# maus-blenano2-mk-1_0_3.net
KiCad netlist of a schematic drawn in EAGLE
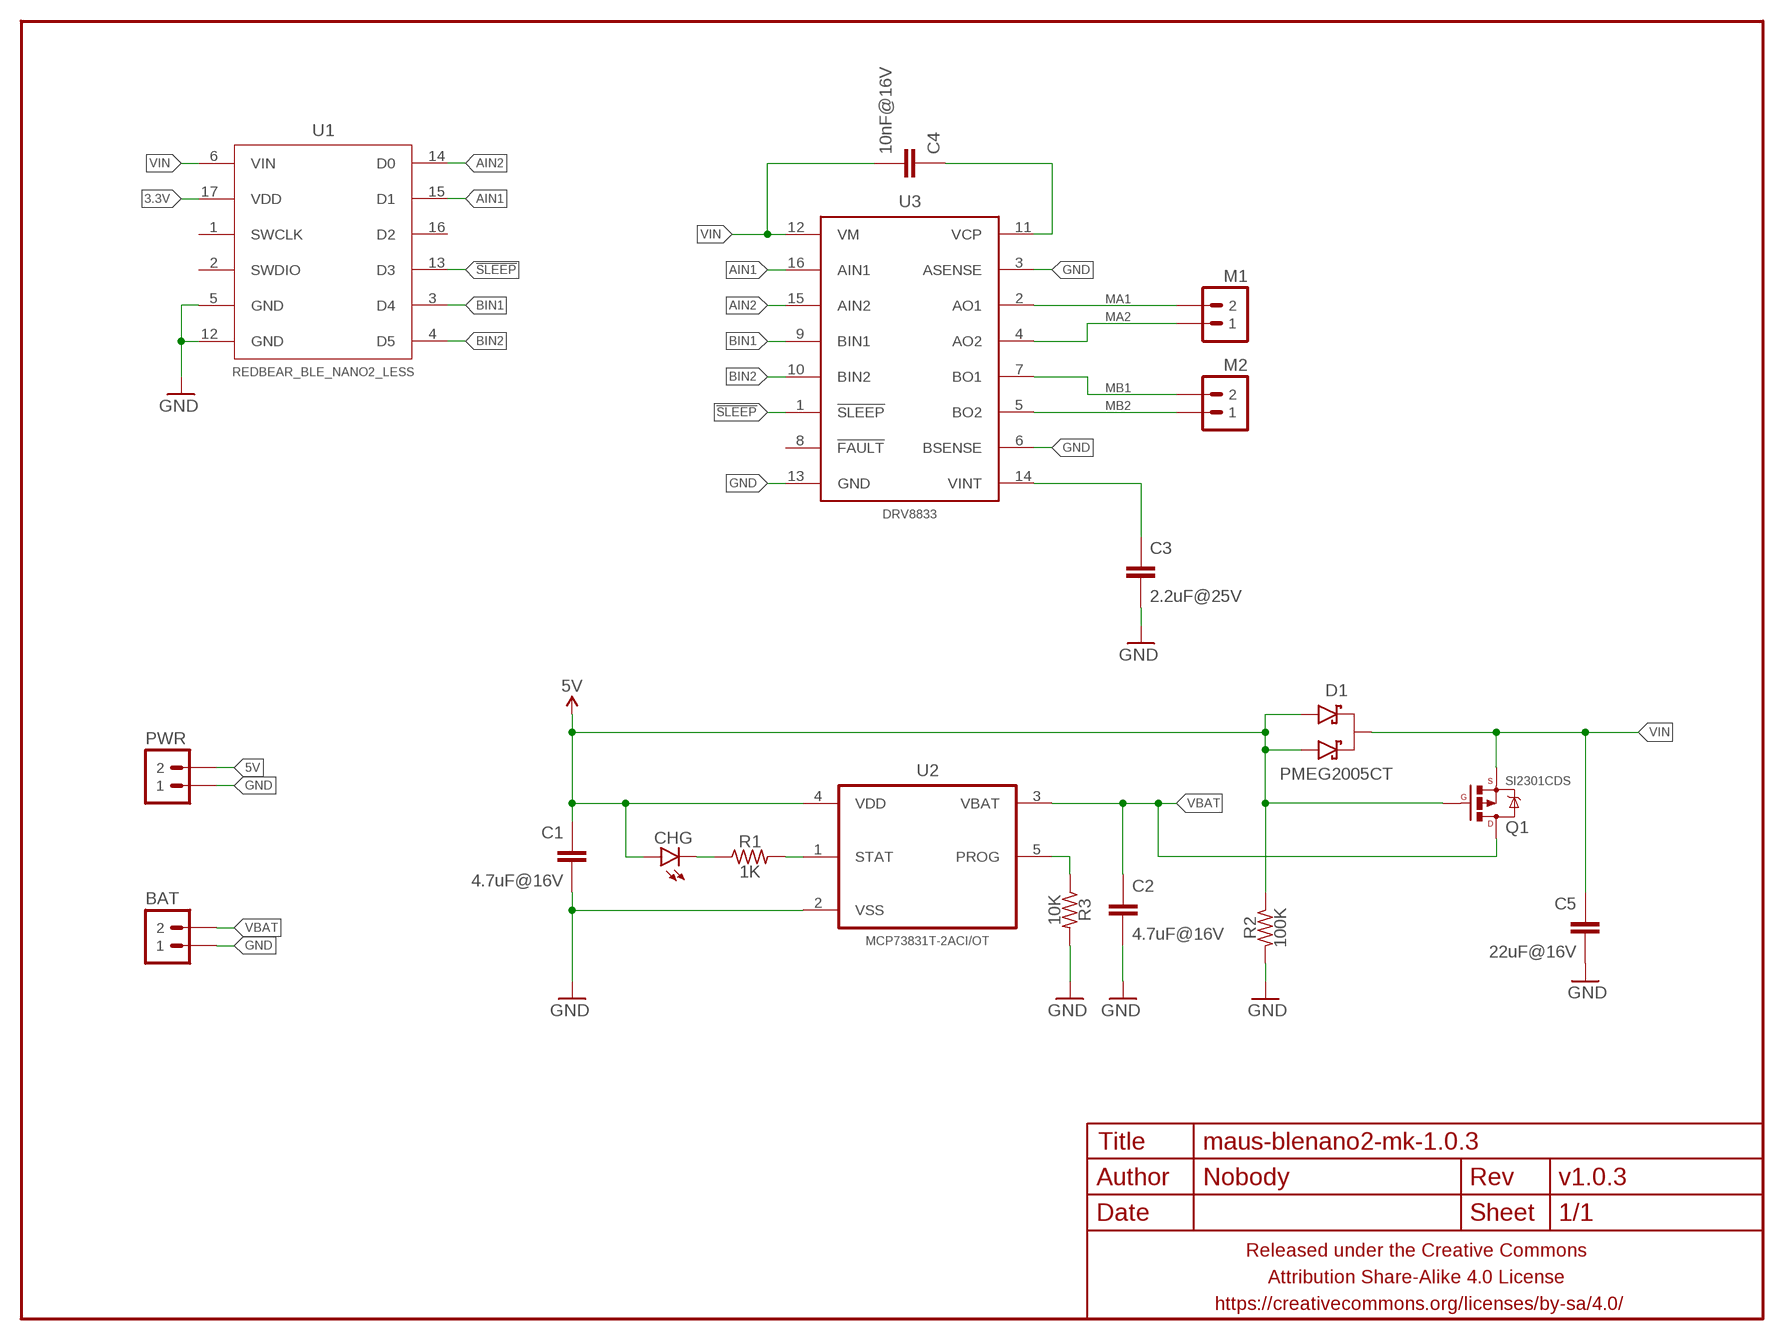
[diagram p0: schematic, sheet 1]

(export (version "E")
  (design (tool "Eeschema 10.0.6"))
  (components
    (comp (ref "BAT")
      (value "M02PTH-2MM")
      (footprint "eagle-import:1X02-2MM-PTH")
      (libsource (lib "eagle-import") (part "M02PTH-2MM"))
    )
    (comp (ref "C1")
      (value "4.7uF@16V")
      (footprint "eagle-import:C0603-TIGHTER")
      (libsource (lib "eagle-import") (part "CAPACITOR-CERAMICC0603-TIGHTER"))
    )
    (comp (ref "C2")
      (value "4.7uF@16V")
      (footprint "eagle-import:C0603-TIGHTER")
      (libsource (lib "eagle-import") (part "CAPACITOR-CERAMICC0603-TIGHTER"))
    )
    (comp (ref "C3")
      (value "2.2uF@25V")
      (footprint "eagle-import:C0603")
      (libsource (lib "eagle-import") (part "CAPACITOR-CERAMICC0603"))
    )
    (comp (ref "C4")
      (value "10nF@16V")
      (footprint "eagle-import:C0402")
      (libsource (lib "eagle-import") (part "CAPACITOR-CERAMICC0402"))
    )
    (comp (ref "C5")
      (value "22uF@16V")
      (footprint "eagle-import:C1206")
      (libsource (lib "eagle-import") (part "CAPACITOR-CERAMICC1206"))
    )
    (comp (ref "CHG")
      (value "LED0603-TIGHT")
      (footprint "eagle-import:LED-0603-TIGHT")
      (libsource (lib "eagle-import") (part "LED0603-TIGHT"))
    )
    (comp (ref "D1")
      (value "PMEG2005CT")
      (footprint "eagle-import:SOT23")
      (libsource (lib "eagle-import") (part "DIODE-SCHOTTKY-DUALPMEG2005CT"))
    )
    (comp (ref "FRAME1")
      (value "FRAME-LETTERNO_PACKAGE")
      (footprint "eagle-import:DUMMY")
      (fields (field (name "VERSION") "v1.0.3") (field (name "DESIGNER") "Nobody"))
      (libsource (lib "eagle-import") (part "FRAME-LETTERNO_PACKAGE"))
    )
    (comp (ref "M1")
      (value "M02PTH-2MM")
      (footprint "eagle-import:1X02-2MM-PTH")
      (libsource (lib "eagle-import") (part "M02PTH-2MM"))
    )
    (comp (ref "M2")
      (value "M02PTH-2MM")
      (footprint "eagle-import:1X02-2MM-PTH")
      (libsource (lib "eagle-import") (part "M02PTH-2MM"))
    )
    (comp (ref "PWR")
      (value "M02PTH-2MM")
      (footprint "eagle-import:1X02-2MM-PTH")
      (libsource (lib "eagle-import") (part "M02PTH-2MM"))
    )
    (comp (ref "Q1")
      (value "SI2301CDS")
      (footprint "eagle-import:SOT23")
      (libsource (lib "eagle-import") (part "MOSFET-PCHANNELSOT-23"))
    )
    (comp (ref "R1")
      (value "1K")
      (footprint "eagle-import:R0603-TIGHTER")
      (libsource (lib "eagle-import") (part "RESISTORR0603-TIGHTER"))
    )
    (comp (ref "R2")
      (value "100K")
      (footprint "eagle-import:R0603-TIGHTER")
      (libsource (lib "eagle-import") (part "RESISTORR0603-TIGHTER"))
    )
    (comp (ref "R3")
      (value "10K")
      (footprint "eagle-import:R0603-TIGHTER")
      (libsource (lib "eagle-import") (part "RESISTORR0603-TIGHTER"))
    )
    (comp (ref "U1")
      (value "REDBEAR_BLE_NANO2_LESS")
      (footprint "eagle-import:REDBEAR_BLE_NANO2_LESS")
      (libsource (lib "eagle-import") (part "REDBEAR_BLE_NANO2_LESS"))
    )
    (comp (ref "U2")
      (value "MCP73831T-2ACI/OT")
      (footprint "eagle-import:SOT95P280X145-5N")
      (libsource (lib "eagle-import") (part "MCP73831T-2ACI/OT"))
    )
    (comp (ref "U3")
      (value "DRV8833")
      (footprint "eagle-import:TSSOP16")
      (libsource (lib "eagle-import") (part "DRV8833PW"))
    )
  )
  (nets
    (net (code "1") (name "/MA1") (class "Default")
      (node (ref "M1") (pin "P$2") (pinfunction "2_P$2") (pintype "passive"))
      (node (ref "U3") (pin "2") (pinfunction "AO1_2") (pintype "bidirectional"))
    )
    (net (code "2") (name "/MA2") (class "Default")
      (node (ref "M1") (pin "P$1") (pinfunction "1_P$1") (pintype "passive"))
      (node (ref "U3") (pin "4") (pinfunction "AO2_4") (pintype "bidirectional"))
    )
    (net (code "3") (name "/MB1") (class "Default")
      (node (ref "M2") (pin "P$2") (pinfunction "2_P$2") (pintype "passive"))
      (node (ref "U3") (pin "7") (pinfunction "BO1_7") (pintype "bidirectional"))
    )
    (net (code "4") (name "/MB2") (class "Default")
      (node (ref "M2") (pin "P$1") (pinfunction "1_P$1") (pintype "passive"))
      (node (ref "U3") (pin "5") (pinfunction "BO2_5") (pintype "bidirectional"))
    )
    (net (code "5") (name "/~{SLEEP}") (class "Default")
      (node (ref "U1") (pin "13") (pinfunction "D3_13") (pintype "bidirectional"))
      (node (ref "U3") (pin "1") (pinfunction "~{SLEEP}_1") (pintype "input"))
    )
    (net (code "6") (name "3.3V") (class "Default")
      (node (ref "U1") (pin "17") (pinfunction "VDD_17") (pintype "bidirectional"))
    )
    (net (code "7") (name "5V") (class "Default")
      (node (ref "C1") (pin "1") (pinfunction "1_1") (pintype "passive"))
      (node (ref "CHG") (pin "A") (pinfunction "A_A") (pintype "passive"))
      (node (ref "D1") (pin "1") (pinfunction "A1_1") (pintype "passive"))
      (node (ref "D1") (pin "2") (pinfunction "A2_2") (pintype "passive"))
      (node (ref "PWR") (pin "P$2") (pinfunction "2_P$2") (pintype "passive"))
      (node (ref "Q1") (pin "1") (pinfunction "G_1") (pintype "passive"))
      (node (ref "R2") (pin "1") (pinfunction "1_1") (pintype "passive"))
      (node (ref "U2") (pin "4") (pinfunction "VDD_4") (pintype "power_in"))
    )
    (net (code "8") (name "AIN1") (class "Default")
      (node (ref "U1") (pin "15") (pinfunction "D1_15") (pintype "bidirectional"))
      (node (ref "U3") (pin "16") (pinfunction "AIN1_16") (pintype "input"))
    )
    (net (code "9") (name "AIN2") (class "Default")
      (node (ref "U1") (pin "14") (pinfunction "D0_14") (pintype "bidirectional"))
      (node (ref "U3") (pin "15") (pinfunction "AIN2_15") (pintype "input"))
    )
    (net (code "10") (name "BIN1") (class "Default")
      (node (ref "U1") (pin "3") (pinfunction "D4_3") (pintype "bidirectional"))
      (node (ref "U3") (pin "9") (pinfunction "BIN1_9") (pintype "input"))
    )
    (net (code "11") (name "BIN2") (class "Default")
      (node (ref "U1") (pin "4") (pinfunction "D5_4") (pintype "bidirectional"))
      (node (ref "U3") (pin "10") (pinfunction "BIN2_10") (pintype "input"))
    )
    (net (code "12") (name "GND") (class "Default")
      (node (ref "BAT") (pin "P$1") (pinfunction "1_P$1") (pintype "passive"))
      (node (ref "C1") (pin "2") (pinfunction "2_2") (pintype "passive"))
      (node (ref "C2") (pin "2") (pinfunction "2_2") (pintype "passive"))
      (node (ref "C3") (pin "2") (pinfunction "2_2") (pintype "passive"))
      (node (ref "C5") (pin "2") (pinfunction "2_2") (pintype "passive"))
      (node (ref "PWR") (pin "P$1") (pinfunction "1_P$1") (pintype "passive"))
      (node (ref "R2") (pin "2") (pinfunction "2_2") (pintype "passive"))
      (node (ref "R3") (pin "2") (pinfunction "2_2") (pintype "passive"))
      (node (ref "U1") (pin "12") (pinfunction "GND_12") (pintype "bidirectional"))
      (node (ref "U1") (pin "5") (pinfunction "GND_5") (pintype "bidirectional"))
      (node (ref "U2") (pin "2") (pinfunction "VSS_2") (pintype "power_in"))
      (node (ref "U3") (pin "13") (pinfunction "GND_13") (pintype "bidirectional"))
      (node (ref "U3") (pin "3") (pinfunction "ASENSE_3") (pintype "bidirectional"))
      (node (ref "U3") (pin "6") (pinfunction "BSENSE_6") (pintype "bidirectional"))
    )
    (net (code "13") (name "Net-(CHG-PadC)") (class "Default")
      (node (ref "CHG") (pin "C") (pinfunction "C_C") (pintype "passive"))
      (node (ref "R1") (pin "1") (pinfunction "1_1") (pintype "passive"))
    )
    (net (code "14") (name "Net-(U2-PROG)") (class "Default")
      (node (ref "R3") (pin "1") (pinfunction "1_1") (pintype "passive"))
      (node (ref "U2") (pin "5") (pinfunction "PROG_5") (pintype "input"))
    )
    (net (code "15") (name "Net-(U2-STAT)") (class "Default")
      (node (ref "R1") (pin "2") (pinfunction "2_2") (pintype "passive"))
      (node (ref "U2") (pin "1") (pinfunction "STAT_1") (pintype "output"))
    )
    (net (code "16") (name "Net-(U3-VCP)") (class "Default")
      (node (ref "C4") (pin "1") (pinfunction "1_1") (pintype "passive"))
      (node (ref "U3") (pin "11") (pinfunction "VCP_11") (pintype "bidirectional"))
    )
    (net (code "17") (name "Net-(U3-VINT)") (class "Default")
      (node (ref "C3") (pin "1") (pinfunction "1_1") (pintype "passive"))
      (node (ref "U3") (pin "14") (pinfunction "VINT_14") (pintype "bidirectional"))
    )
    (net (code "18") (name "VBAT") (class "Default")
      (node (ref "BAT") (pin "P$2") (pinfunction "2_P$2") (pintype "passive"))
      (node (ref "C2") (pin "1") (pinfunction "1_1") (pintype "passive"))
      (node (ref "Q1") (pin "3") (pinfunction "D_3") (pintype "passive"))
      (node (ref "U2") (pin "3") (pinfunction "VBAT_3") (pintype "output"))
    )
    (net (code "19") (name "VIN") (class "Default")
      (node (ref "C4") (pin "2") (pinfunction "2_2") (pintype "passive"))
      (node (ref "C5") (pin "1") (pinfunction "1_1") (pintype "passive"))
      (node (ref "D1") (pin "3") (pinfunction "K_3") (pintype "passive"))
      (node (ref "Q1") (pin "2") (pinfunction "S_2") (pintype "passive"))
      (node (ref "U1") (pin "6") (pinfunction "VIN_6") (pintype "bidirectional"))
      (node (ref "U3") (pin "12") (pinfunction "VM_12") (pintype "bidirectional"))
    )
    (net (code "20") (name "unconnected-(U1-D2-Pad16)") (class "Default")
      (node (ref "U1") (pin "16") (pinfunction "D2_16") (pintype "bidirectional"))
    )
    (net (code "21") (name "unconnected-(U1-SWCLK-Pad1)") (class "Default")
      (node (ref "U1") (pin "1") (pinfunction "SWCLK_1") (pintype "bidirectional"))
    )
    (net (code "22") (name "unconnected-(U1-SWDIO-Pad2)") (class "Default")
      (node (ref "U1") (pin "2") (pinfunction "SWDIO_2") (pintype "bidirectional"))
    )
    (net (code "23") (name "unconnected-(U3-~{FAULT}-Pad8)") (class "Default")
      (node (ref "U3") (pin "8") (pinfunction "~{FAULT}_8") (pintype "output"))
    )
  )
)
